# driver_gliderscore.net
KiCad netlist of a schematic drawn in EAGLE
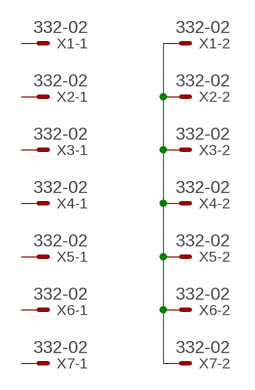
[diagram p0: schematic, sheet 1]
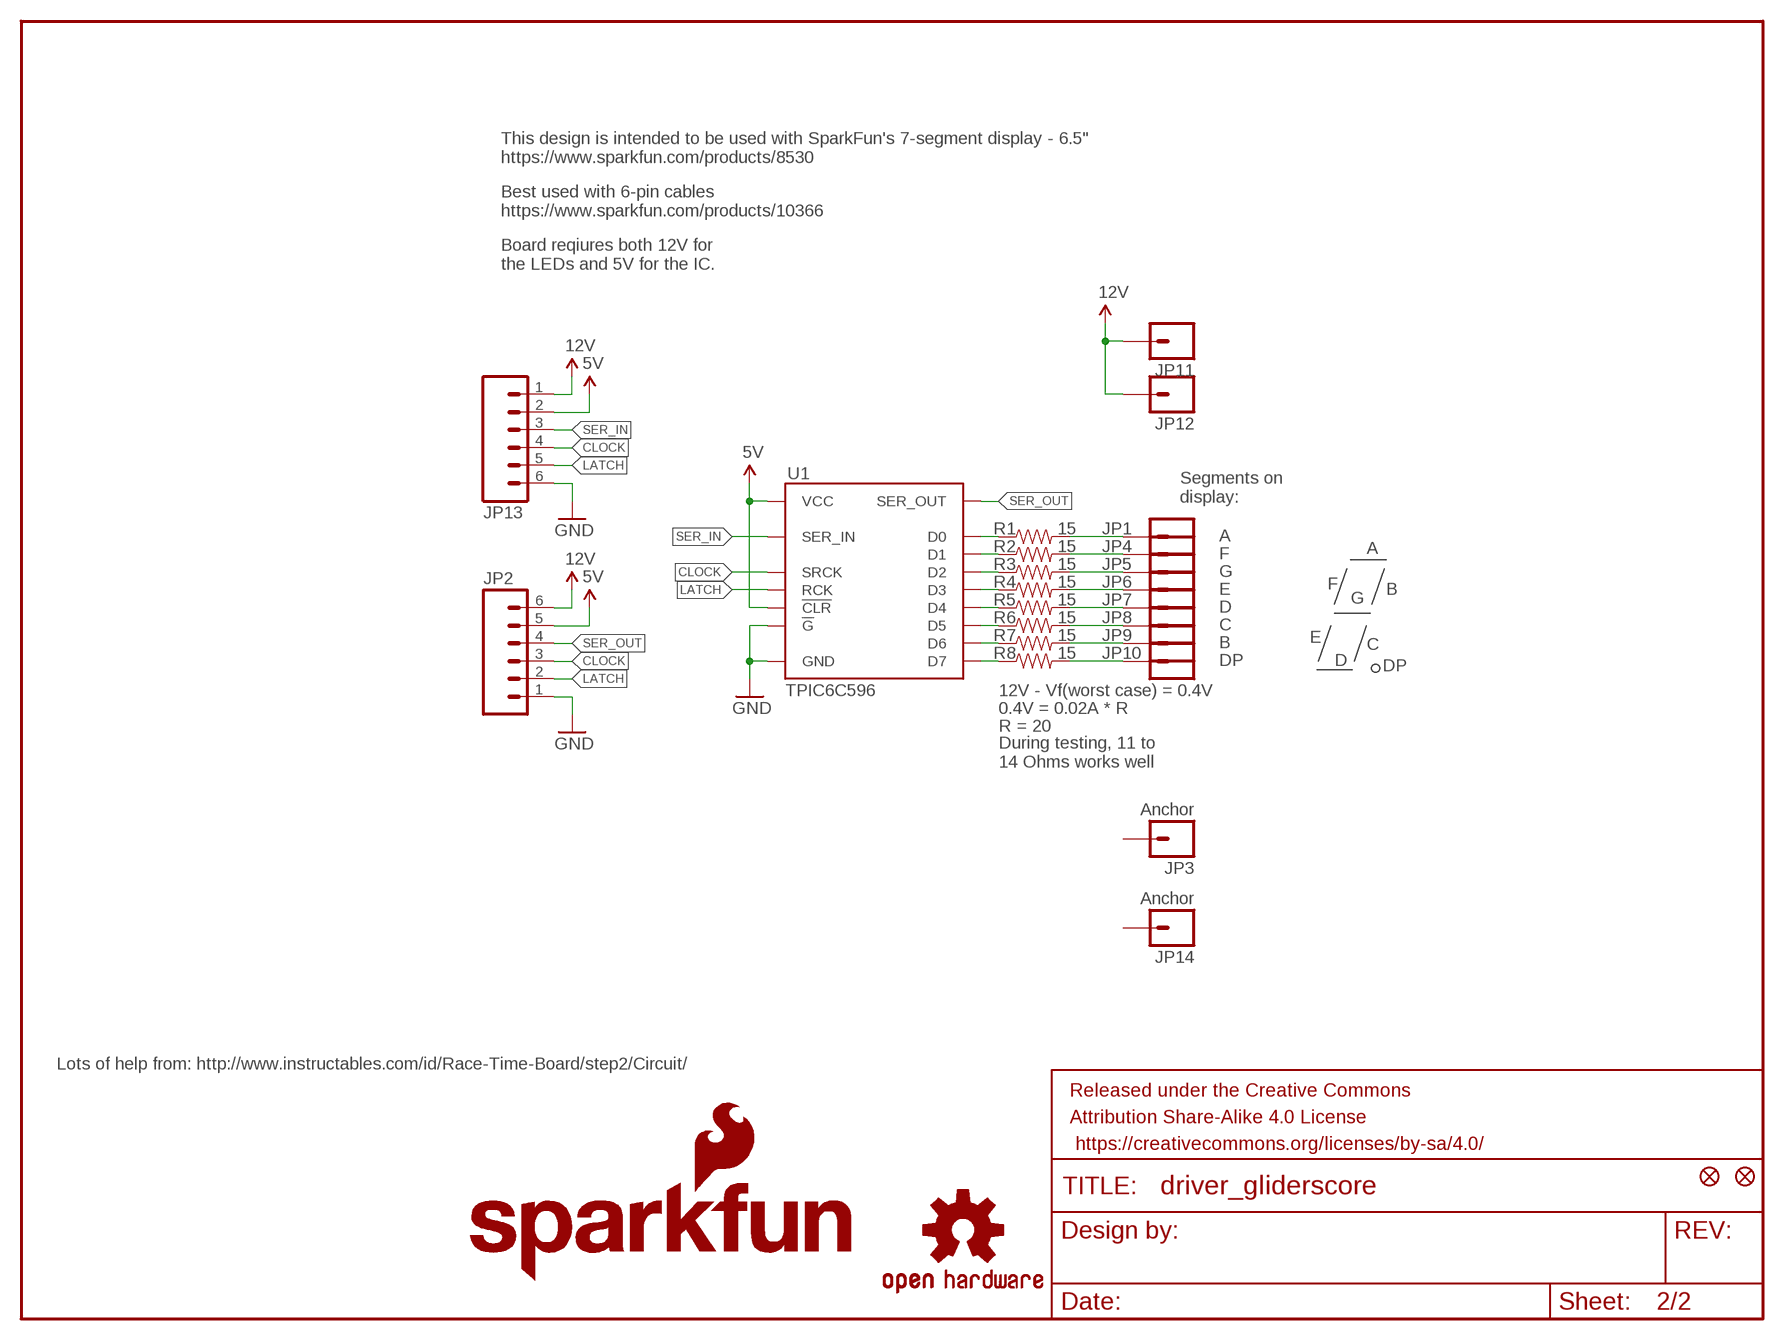
[diagram p1: schematic, sheet 2]

(export (version "E")
  (design (tool "Eeschema 10.0.6"))
  (components
    (comp (ref "X1")
      (value "332-02")
      (footprint "eagle-import:332-02")
      (libsource (lib "eagle-import") (part "332-02"))
    )
    (comp (ref "X2")
      (value "332-02")
      (footprint "eagle-import:332-02")
      (libsource (lib "eagle-import") (part "332-02"))
    )
    (comp (ref "X3")
      (value "332-02")
      (footprint "eagle-import:332-02")
      (libsource (lib "eagle-import") (part "332-02"))
    )
    (comp (ref "X4")
      (value "332-02")
      (footprint "eagle-import:332-02")
      (libsource (lib "eagle-import") (part "332-02"))
    )
    (comp (ref "X5")
      (value "332-02")
      (footprint "eagle-import:332-02")
      (libsource (lib "eagle-import") (part "332-02"))
    )
    (comp (ref "X6")
      (value "332-02")
      (footprint "eagle-import:332-02")
      (libsource (lib "eagle-import") (part "332-02"))
    )
    (comp (ref "X7")
      (value "332-02")
      (footprint "eagle-import:332-02")
      (libsource (lib "eagle-import") (part "332-02"))
    )
    (comp (ref "FID1")
      (value "FIDUCIAL1X2")
      (footprint "eagle-import:FIDUCIAL-1X2")
      (libsource (lib "eagle-import") (part "FIDUCIAL1X2"))
    )
    (comp (ref "FID2")
      (value "FIDUCIAL1X2")
      (footprint "eagle-import:FIDUCIAL-1X2")
      (libsource (lib "eagle-import") (part "FIDUCIAL1X2"))
    )
    (comp (ref "FRAME1")
      (value "FRAME-LETTER")
      (footprint "eagle-import:CREATIVE_COMMONS")
      (fields (field (name "DESIGNER") "N. Seidle") (field (name "VERSION") "v10"))
      (libsource (lib "eagle-import") (part "FRAME-LETTER"))
    )
    (comp (ref "JP1")
      (value "M01PTH_LONGPAD")
      (footprint "eagle-import:1X01_LONGPAD")
      (libsource (lib "eagle-import") (part "M01PTH_LONGPAD"))
    )
    (comp (ref "JP2")
      (value "M06SMD")
      (footprint "eagle-import:1X06-SMD")
      (libsource (lib "eagle-import") (part "M06SMD"))
    )
    (comp (ref "JP3")
      (value "Anchor")
      (footprint "eagle-import:1X01_LONGPAD")
      (libsource (lib "eagle-import") (part "M01PTH_LONGPAD"))
    )
    (comp (ref "JP4")
      (value "M01PTH_LONGPAD")
      (footprint "eagle-import:1X01_LONGPAD")
      (libsource (lib "eagle-import") (part "M01PTH_LONGPAD"))
    )
    (comp (ref "JP5")
      (value "M01PTH_LONGPAD")
      (footprint "eagle-import:1X01_LONGPAD")
      (libsource (lib "eagle-import") (part "M01PTH_LONGPAD"))
    )
    (comp (ref "JP6")
      (value "M01PTH_LONGPAD")
      (footprint "eagle-import:1X01_LONGPAD")
      (libsource (lib "eagle-import") (part "M01PTH_LONGPAD"))
    )
    (comp (ref "JP7")
      (value "M01PTH_LONGPAD")
      (footprint "eagle-import:1X01_LONGPAD")
      (libsource (lib "eagle-import") (part "M01PTH_LONGPAD"))
    )
    (comp (ref "JP8")
      (value "M01PTH_LONGPAD")
      (footprint "eagle-import:1X01_LONGPAD")
      (libsource (lib "eagle-import") (part "M01PTH_LONGPAD"))
    )
    (comp (ref "JP9")
      (value "M01PTH_LONGPAD")
      (footprint "eagle-import:1X01_LONGPAD")
      (libsource (lib "eagle-import") (part "M01PTH_LONGPAD"))
    )
    (comp (ref "JP10")
      (value "M01PTH_LONGPAD")
      (footprint "eagle-import:1X01_LONGPAD")
      (libsource (lib "eagle-import") (part "M01PTH_LONGPAD"))
    )
    (comp (ref "JP11")
      (value "M01PTH_LONGPAD")
      (footprint "eagle-import:1X01_LONGPAD")
      (libsource (lib "eagle-import") (part "M01PTH_LONGPAD"))
    )
    (comp (ref "JP12")
      (value "M01PTH_LONGPAD")
      (footprint "eagle-import:1X01_LONGPAD")
      (libsource (lib "eagle-import") (part "M01PTH_LONGPAD"))
    )
    (comp (ref "JP13")
      (value "M06SMD")
      (footprint "eagle-import:1X06-SMD")
      (libsource (lib "eagle-import") (part "M06SMD"))
    )
    (comp (ref "JP14")
      (value "Anchor")
      (footprint "eagle-import:1X01_LONGPAD")
      (libsource (lib "eagle-import") (part "M01PTH_LONGPAD"))
    )
    (comp (ref "LOGO1")
      (value "SFE_LOGO_NAME_FLAME.1_INCH")
      (footprint "eagle-import:SFE_LOGO_NAME_FLAME_.1")
      (libsource (lib "eagle-import") (part "SFE_LOGO_NAME_FLAME.1_INCH"))
    )
    (comp (ref "LOGO2")
      (value "OSHW-LOGOS")
      (footprint "eagle-import:OSHW-LOGO-S")
      (libsource (lib "eagle-import") (part "OSHW-LOGOS"))
    )
    (comp (ref "R1")
      (value "15")
      (footprint "eagle-import:0603-RES")
      (libsource (lib "eagle-import") (part "15OHM-1/10W-1%(0603)0603"))
    )
    (comp (ref "R2")
      (value "15")
      (footprint "eagle-import:0603-RES")
      (libsource (lib "eagle-import") (part "15OHM-1/10W-1%(0603)0603"))
    )
    (comp (ref "R3")
      (value "15")
      (footprint "eagle-import:0603-RES")
      (libsource (lib "eagle-import") (part "15OHM-1/10W-1%(0603)0603"))
    )
    (comp (ref "R4")
      (value "15")
      (footprint "eagle-import:0603-RES")
      (libsource (lib "eagle-import") (part "15OHM-1/10W-1%(0603)0603"))
    )
    (comp (ref "R5")
      (value "15")
      (footprint "eagle-import:0603-RES")
      (libsource (lib "eagle-import") (part "15OHM-1/10W-1%(0603)0603"))
    )
    (comp (ref "R6")
      (value "15")
      (footprint "eagle-import:0603-RES")
      (libsource (lib "eagle-import") (part "15OHM-1/10W-1%(0603)0603"))
    )
    (comp (ref "R7")
      (value "15")
      (footprint "eagle-import:0603-RES")
      (libsource (lib "eagle-import") (part "15OHM-1/10W-1%(0603)0603"))
    )
    (comp (ref "R8")
      (value "15")
      (footprint "eagle-import:0603-RES")
      (libsource (lib "eagle-import") (part "15OHM-1/10W-1%(0603)0603"))
    )
    (comp (ref "U1")
      (value "TPIC6C596")
      (footprint "eagle-import:SO016")
      (libsource (lib "eagle-import") (part "TPIC6C596SOIC"))
    )
  )
  (nets
    (net (code "1") (name "5V") (class "Default")
      (node (ref "JP13") (pin "2") (pinfunction "2_2") (pintype "passive"))
      (node (ref "JP2") (pin "5") (pinfunction "5_5") (pintype "passive"))
      (node (ref "U1") (pin "1") (pinfunction "VCC_1") (pintype "power_in"))
      (node (ref "U1") (pin "7") (pinfunction "~{CLR}_7") (pintype "input"))
    )
    (net (code "2") (name "12V") (class "Default")
      (node (ref "JP11") (pin "1") (pinfunction "1_1") (pintype "passive"))
      (node (ref "JP12") (pin "1") (pinfunction "1_1") (pintype "passive"))
      (node (ref "JP13") (pin "1") (pinfunction "1_1") (pintype "passive"))
      (node (ref "JP2") (pin "6") (pinfunction "6_6") (pintype "passive"))
    )
    (net (code "3") (name "CLOCK") (class "Default")
      (node (ref "JP13") (pin "4") (pinfunction "4_4") (pintype "passive"))
      (node (ref "JP2") (pin "3") (pinfunction "3_3") (pintype "passive"))
      (node (ref "U1") (pin "15") (pinfunction "SRCK_15") (pintype "input"))
    )
    (net (code "4") (name "GND") (class "Default")
      (node (ref "JP13") (pin "6") (pinfunction "6_6") (pintype "passive"))
      (node (ref "JP2") (pin "1") (pinfunction "1_1") (pintype "passive"))
      (node (ref "U1") (pin "16") (pinfunction "GND_16") (pintype "power_in"))
      (node (ref "U1") (pin "8") (pinfunction "~{G}_8") (pintype "input"))
    )
    (net (code "5") (name "LATCH") (class "Default")
      (node (ref "JP13") (pin "5") (pinfunction "5_5") (pintype "passive"))
      (node (ref "JP2") (pin "2") (pinfunction "2_2") (pintype "passive"))
      (node (ref "U1") (pin "10") (pinfunction "RCK_10") (pintype "input"))
    )
    (net (code "6") (name "Net-(JP1-Pad1)") (class "Default")
      (node (ref "JP1") (pin "1") (pinfunction "1_1") (pintype "passive"))
      (node (ref "R1") (pin "2") (pinfunction "2_2") (pintype "passive"))
    )
    (net (code "7") (name "Net-(JP4-Pad1)") (class "Default")
      (node (ref "JP4") (pin "1") (pinfunction "1_1") (pintype "passive"))
      (node (ref "R2") (pin "2") (pinfunction "2_2") (pintype "passive"))
    )
    (net (code "8") (name "Net-(JP5-Pad1)") (class "Default")
      (node (ref "JP5") (pin "1") (pinfunction "1_1") (pintype "passive"))
      (node (ref "R3") (pin "2") (pinfunction "2_2") (pintype "passive"))
    )
    (net (code "9") (name "Net-(JP6-Pad1)") (class "Default")
      (node (ref "JP6") (pin "1") (pinfunction "1_1") (pintype "passive"))
      (node (ref "R4") (pin "2") (pinfunction "2_2") (pintype "passive"))
    )
    (net (code "10") (name "Net-(JP7-Pad1)") (class "Default")
      (node (ref "JP7") (pin "1") (pinfunction "1_1") (pintype "passive"))
      (node (ref "R5") (pin "2") (pinfunction "2_2") (pintype "passive"))
    )
    (net (code "11") (name "Net-(JP8-Pad1)") (class "Default")
      (node (ref "JP8") (pin "1") (pinfunction "1_1") (pintype "passive"))
      (node (ref "R6") (pin "2") (pinfunction "2_2") (pintype "passive"))
    )
    (net (code "12") (name "Net-(JP9-Pad1)") (class "Default")
      (node (ref "JP9") (pin "1") (pinfunction "1_1") (pintype "passive"))
      (node (ref "R7") (pin "2") (pinfunction "2_2") (pintype "passive"))
    )
    (net (code "13") (name "Net-(JP10-Pad1)") (class "Default")
      (node (ref "JP10") (pin "1") (pinfunction "1_1") (pintype "passive"))
      (node (ref "R8") (pin "2") (pinfunction "2_2") (pintype "passive"))
    )
    (net (code "14") (name "Net-(U1-D0)") (class "Default")
      (node (ref "R1") (pin "1") (pinfunction "1_1") (pintype "passive"))
      (node (ref "U1") (pin "3") (pinfunction "D0_3") (pintype "output"))
    )
    (net (code "15") (name "Net-(U1-D1)") (class "Default")
      (node (ref "R2") (pin "1") (pinfunction "1_1") (pintype "passive"))
      (node (ref "U1") (pin "4") (pinfunction "D1_4") (pintype "output"))
    )
    (net (code "16") (name "Net-(U1-D2)") (class "Default")
      (node (ref "R3") (pin "1") (pinfunction "1_1") (pintype "passive"))
      (node (ref "U1") (pin "5") (pinfunction "D2_5") (pintype "output"))
    )
    (net (code "17") (name "Net-(U1-D3)") (class "Default")
      (node (ref "R4") (pin "1") (pinfunction "1_1") (pintype "passive"))
      (node (ref "U1") (pin "6") (pinfunction "D3_6") (pintype "output"))
    )
    (net (code "18") (name "Net-(U1-D4)") (class "Default")
      (node (ref "R5") (pin "1") (pinfunction "1_1") (pintype "passive"))
      (node (ref "U1") (pin "11") (pinfunction "D4_11") (pintype "output"))
    )
    (net (code "19") (name "Net-(U1-D5)") (class "Default")
      (node (ref "R6") (pin "1") (pinfunction "1_1") (pintype "passive"))
      (node (ref "U1") (pin "12") (pinfunction "D5_12") (pintype "output"))
    )
    (net (code "20") (name "Net-(U1-D6)") (class "Default")
      (node (ref "R7") (pin "1") (pinfunction "1_1") (pintype "passive"))
      (node (ref "U1") (pin "13") (pinfunction "D6_13") (pintype "output"))
    )
    (net (code "21") (name "Net-(U1-D7)") (class "Default")
      (node (ref "R8") (pin "1") (pinfunction "1_1") (pintype "passive"))
      (node (ref "U1") (pin "14") (pinfunction "D7_14") (pintype "output"))
    )
    (net (code "22") (name "Net-(X1B-S)") (class "Default")
      (node (ref "X1") (pin "2") (pinfunction "S_2") (pintype "passive"))
      (node (ref "X2") (pin "2") (pinfunction "S_2") (pintype "passive"))
      (node (ref "X3") (pin "2") (pinfunction "S_2") (pintype "passive"))
      (node (ref "X4") (pin "2") (pinfunction "S_2") (pintype "passive"))
      (node (ref "X5") (pin "2") (pinfunction "S_2") (pintype "passive"))
      (node (ref "X6") (pin "2") (pinfunction "S_2") (pintype "passive"))
      (node (ref "X7") (pin "2") (pinfunction "S_2") (pintype "passive"))
    )
    (net (code "23") (name "SER_IN") (class "Default")
      (node (ref "JP13") (pin "3") (pinfunction "3_3") (pintype "passive"))
      (node (ref "U1") (pin "2") (pinfunction "SER_IN_2") (pintype "input"))
    )
    (net (code "24") (name "SER_OUT") (class "Default")
      (node (ref "JP2") (pin "4") (pinfunction "4_4") (pintype "passive"))
      (node (ref "U1") (pin "9") (pinfunction "SER_OUT_9") (pintype "output"))
    )
    (net (code "25") (name "unconnected-(JP3-Pad1)") (class "Default")
      (node (ref "JP3") (pin "1") (pinfunction "1_1") (pintype "passive"))
    )
    (net (code "26") (name "unconnected-(JP14-Pad1)") (class "Default")
      (node (ref "JP14") (pin "1") (pinfunction "1_1") (pintype "passive"))
    )
    (net (code "27") (name "unconnected-(X1A-S-Pad1)") (class "Default")
      (node (ref "X1") (pin "1") (pinfunction "S_1") (pintype "passive"))
    )
    (net (code "28") (name "unconnected-(X2A-S-Pad1)") (class "Default")
      (node (ref "X2") (pin "1") (pinfunction "S_1") (pintype "passive"))
    )
    (net (code "29") (name "unconnected-(X3A-S-Pad1)") (class "Default")
      (node (ref "X3") (pin "1") (pinfunction "S_1") (pintype "passive"))
    )
    (net (code "30") (name "unconnected-(X4A-S-Pad1)") (class "Default")
      (node (ref "X4") (pin "1") (pinfunction "S_1") (pintype "passive"))
    )
    (net (code "31") (name "unconnected-(X5A-S-Pad1)") (class "Default")
      (node (ref "X5") (pin "1") (pinfunction "S_1") (pintype "passive"))
    )
    (net (code "32") (name "unconnected-(X6A-S-Pad1)") (class "Default")
      (node (ref "X6") (pin "1") (pinfunction "S_1") (pintype "passive"))
    )
    (net (code "33") (name "unconnected-(X7A-S-Pad1)") (class "Default")
      (node (ref "X7") (pin "1") (pinfunction "S_1") (pintype "passive"))
    )
  )
)
